# module_connector.net
KiCad netlist of a schematic drawn in EAGLE
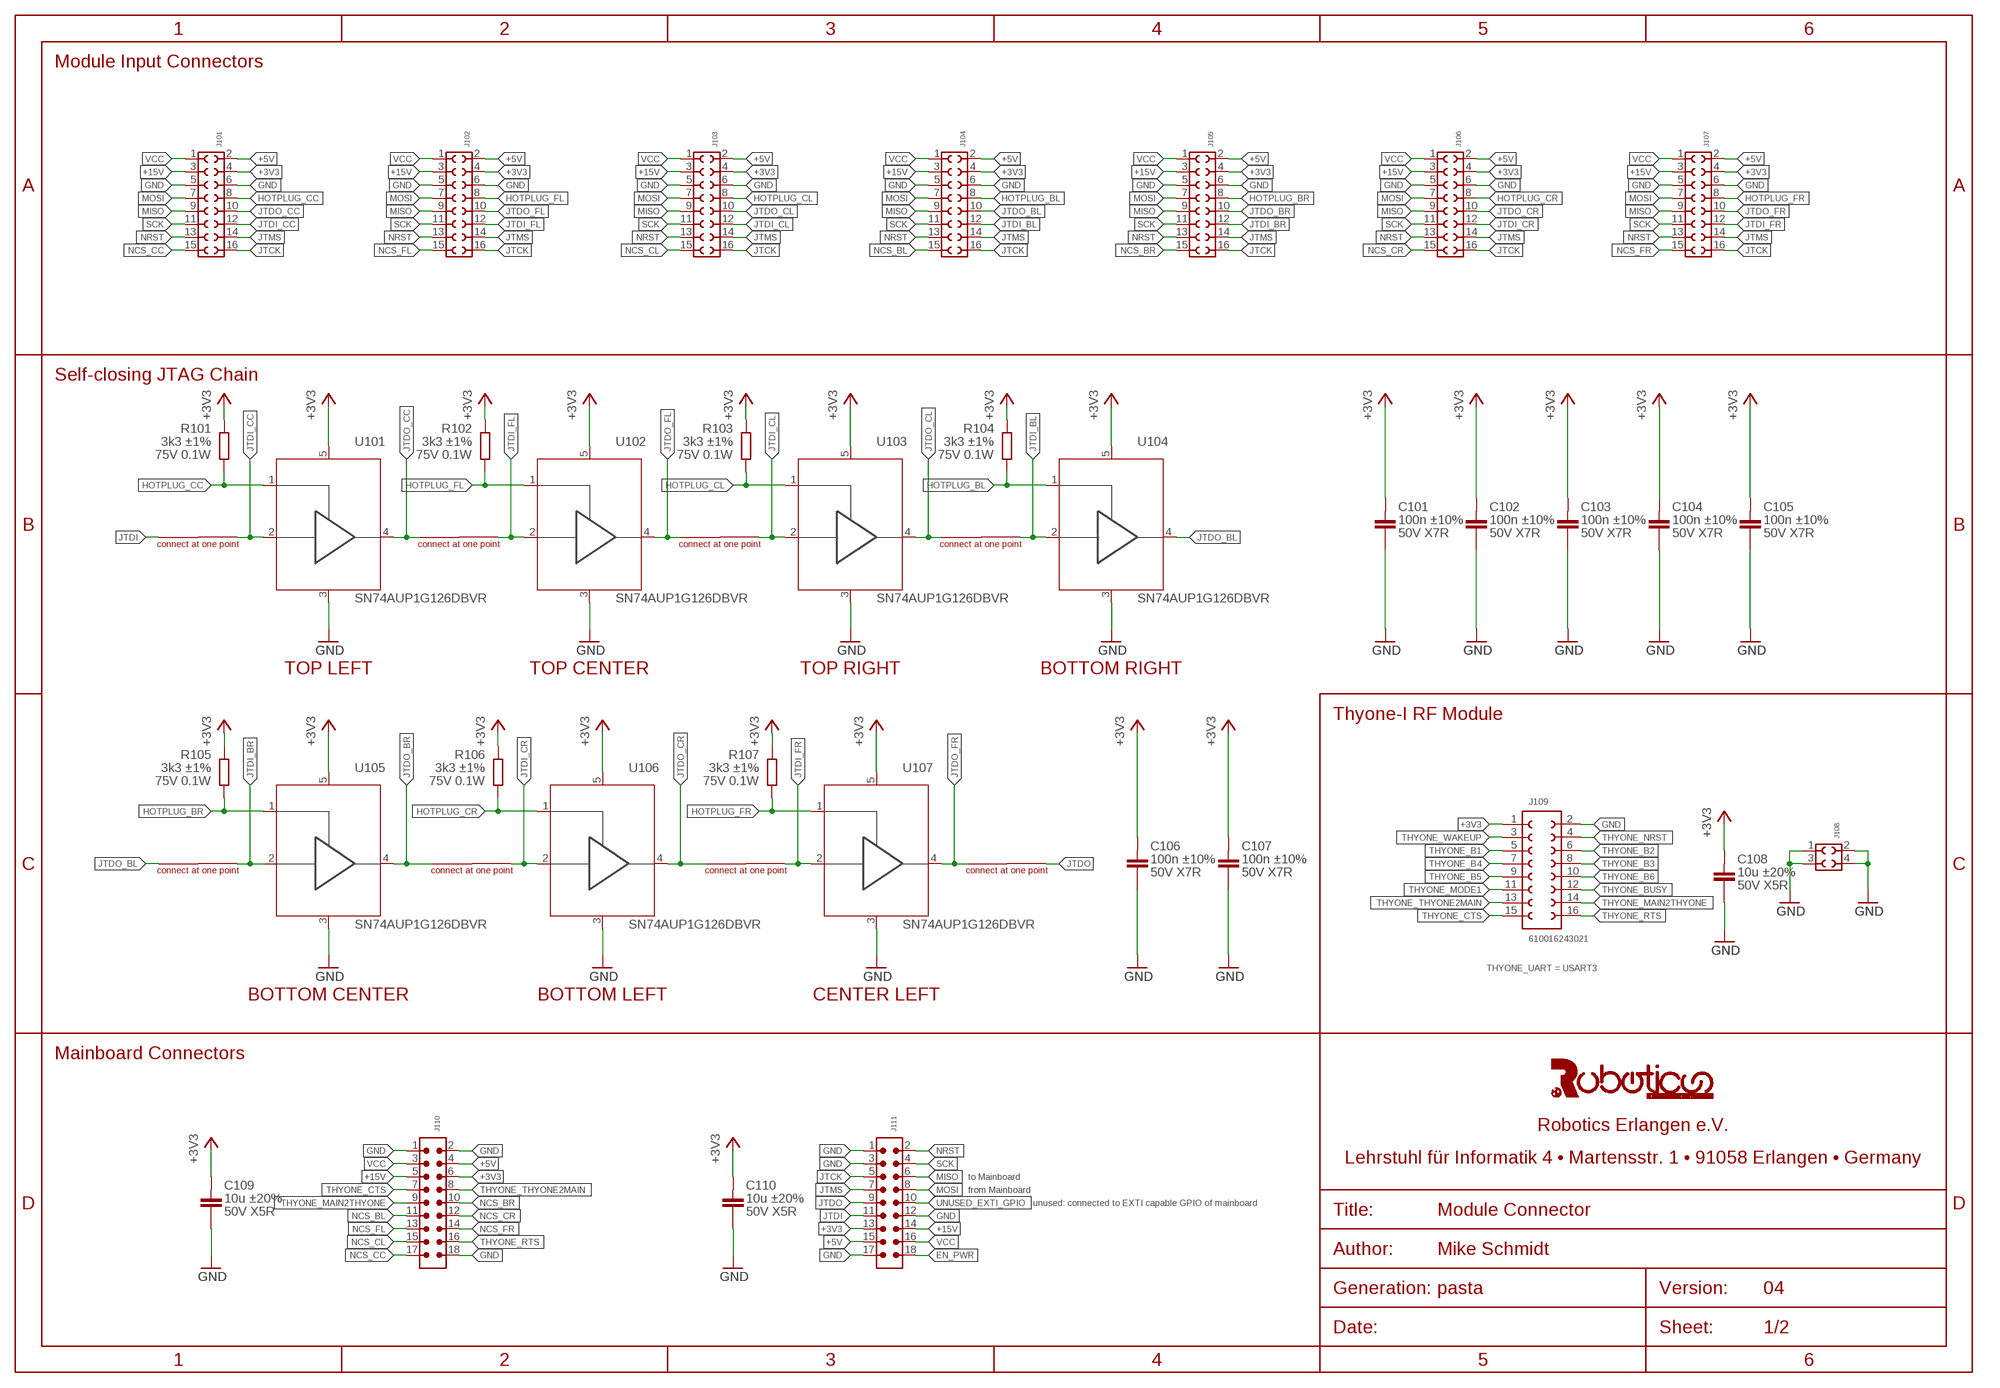
[diagram p0: schematic, sheet 1]
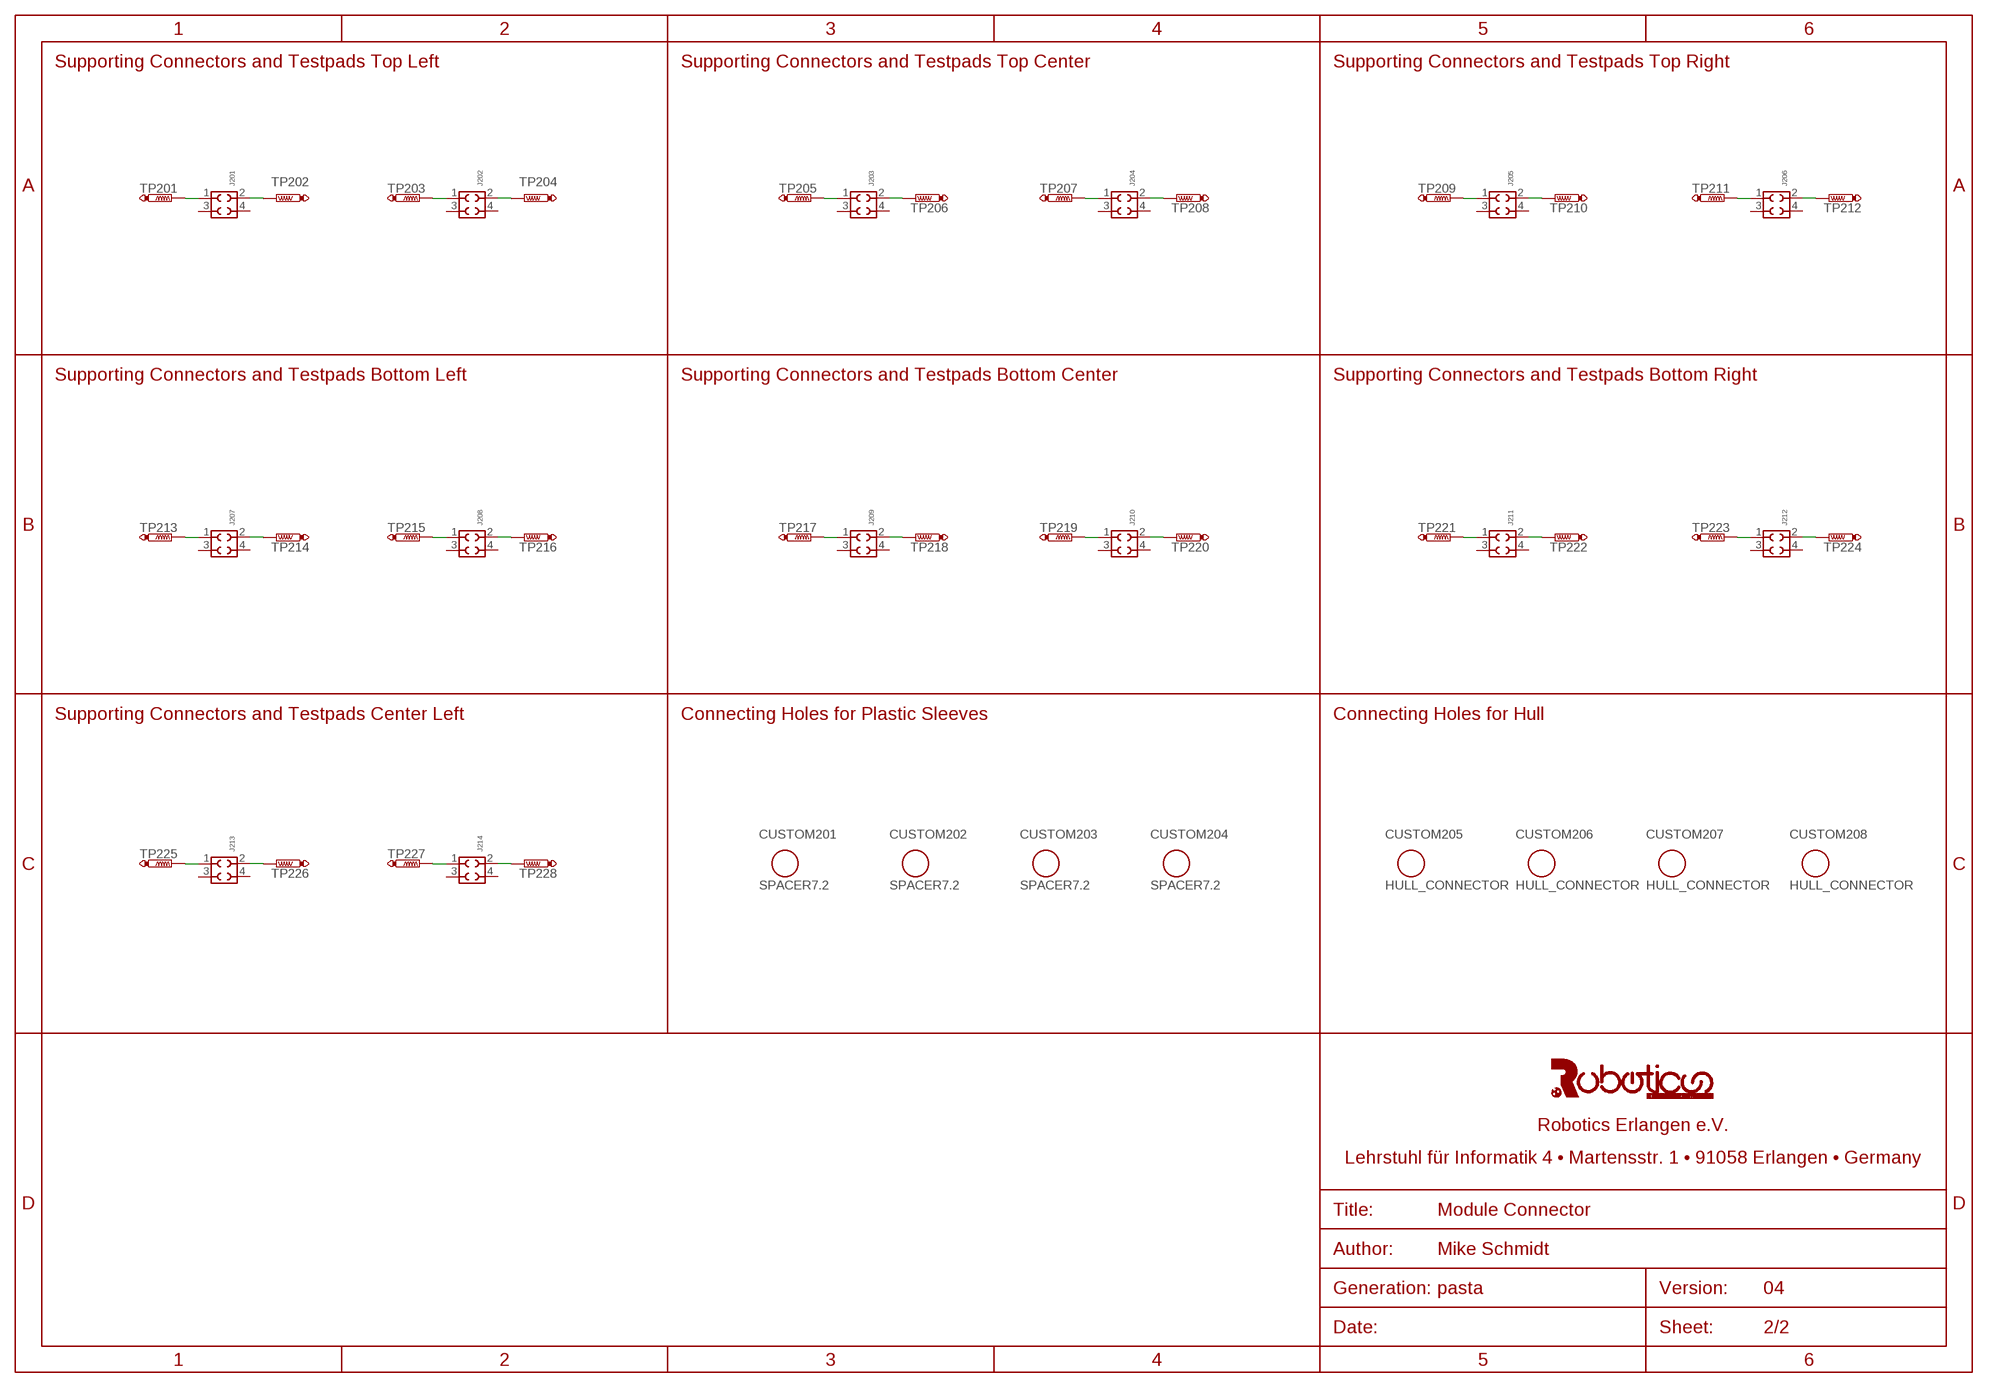
[diagram p1: schematic, sheet 2]

(export (version "E")
  (design (tool "Eeschema 10.0.6"))
  (components
    (comp (ref "C101")
      (value "100n ±10% 50V X7R")
      (footprint "eagle-import:C0603")
      (fields
        (field (name "LINE1") "100n ±10%")
        (field (name "LINE2") "50V X7R")
        (field (name "MF") "Würth Elektronik")
        (field (name "MPN") "885012206095")
        (field (name "TOLERANCE") "±10%")
      )
      (libsource (lib "eagle-import") (part "C(?)0603100NF,50V,"))
    )
    (comp (ref "C102")
      (value "100n ±10% 50V X7R")
      (footprint "eagle-import:C0603")
      (fields
        (field (name "LINE1") "100n ±10%")
        (field (name "LINE2") "50V X7R")
        (field (name "MF") "Würth Elektronik")
        (field (name "MPN") "885012206095")
        (field (name "TOLERANCE") "±10%")
      )
      (libsource (lib "eagle-import") (part "C(?)0603100NF,50V,"))
    )
    (comp (ref "C103")
      (value "100n ±10% 50V X7R")
      (footprint "eagle-import:C0603")
      (fields
        (field (name "LINE1") "100n ±10%")
        (field (name "LINE2") "50V X7R")
        (field (name "MF") "Würth Elektronik")
        (field (name "MPN") "885012206095")
        (field (name "TOLERANCE") "±10%")
      )
      (libsource (lib "eagle-import") (part "C(?)0603100NF,50V,"))
    )
    (comp (ref "C104")
      (value "100n ±10% 50V X7R")
      (footprint "eagle-import:C0603")
      (fields
        (field (name "LINE1") "100n ±10%")
        (field (name "LINE2") "50V X7R")
        (field (name "MF") "Würth Elektronik")
        (field (name "MPN") "885012206095")
        (field (name "TOLERANCE") "±10%")
      )
      (libsource (lib "eagle-import") (part "C(?)0603100NF,50V,"))
    )
    (comp (ref "C105")
      (value "100n ±10% 50V X7R")
      (footprint "eagle-import:C0603")
      (fields
        (field (name "LINE1") "100n ±10%")
        (field (name "LINE2") "50V X7R")
        (field (name "MF") "Würth Elektronik")
        (field (name "MPN") "885012206095")
        (field (name "TOLERANCE") "±10%")
      )
      (libsource (lib "eagle-import") (part "C(?)0603100NF,50V,"))
    )
    (comp (ref "C106")
      (value "100n ±10% 50V X7R")
      (footprint "eagle-import:C0603")
      (fields
        (field (name "LINE1") "100n ±10%")
        (field (name "LINE2") "50V X7R")
        (field (name "MF") "Würth Elektronik")
        (field (name "MPN") "885012206095")
        (field (name "TOLERANCE") "±10%")
      )
      (libsource (lib "eagle-import") (part "C(?)0603100NF,50V,"))
    )
    (comp (ref "C107")
      (value "100n ±10% 50V X7R")
      (footprint "eagle-import:C0603")
      (fields
        (field (name "LINE1") "100n ±10%")
        (field (name "LINE2") "50V X7R")
        (field (name "MF") "Würth Elektronik")
        (field (name "MPN") "885012206095")
        (field (name "TOLERANCE") "±10%")
      )
      (libsource (lib "eagle-import") (part "C(?)0603100NF,50V,"))
    )
    (comp (ref "C108")
      (value "10u ±20% 50V X5R")
      (footprint "eagle-import:C1206")
      (fields
        (field (name "LINE1") "10u ±20%")
        (field (name "LINE2") "50V X5R")
        (field (name "MF") "Samsung")
        (field (name "MPN") "CL31A106MBHNNNE")
        (field (name "TOLERANCE") "±20%")
      )
      (libsource (lib "eagle-import") (part "C(?)120610UF,50V,"))
    )
    (comp (ref "C109")
      (value "10u ±20% 50V X5R")
      (footprint "eagle-import:C1206")
      (fields
        (field (name "LINE1") "10u ±20%")
        (field (name "LINE2") "50V X5R")
        (field (name "MF") "Samsung")
        (field (name "MPN") "CL31A106MBHNNNE")
        (field (name "TOLERANCE") "±20%")
      )
      (libsource (lib "eagle-import") (part "C(?)120610UF,50V,"))
    )
    (comp (ref "C110")
      (value "10u ±20% 50V X5R")
      (footprint "eagle-import:C1206")
      (fields
        (field (name "LINE1") "10u ±20%")
        (field (name "LINE2") "50V X5R")
        (field (name "MF") "Samsung")
        (field (name "MPN") "CL31A106MBHNNNE")
        (field (name "TOLERANCE") "±20%")
      )
      (libsource (lib "eagle-import") (part "C(?)120610UF,50V,"))
    )
    (comp (ref "J101")
      (value "6100XX243021_610016243021")
      (footprint "eagle-import:610016243021")
      (fields (field (name "MF") "Würth Elektronik") (field (name "MPN") "610016243021"))
      (libsource (lib "eagle-import") (part "6100XX243021_610016243021"))
    )
    (comp (ref "J102")
      (value "6100XX243021_610016243021")
      (footprint "eagle-import:610016243021")
      (fields (field (name "MF") "Würth Elektronik") (field (name "MPN") "610016243021"))
      (libsource (lib "eagle-import") (part "6100XX243021_610016243021"))
    )
    (comp (ref "J103")
      (value "6100XX243021_610016243021")
      (footprint "eagle-import:610016243021")
      (fields (field (name "MF") "Würth Elektronik") (field (name "MPN") "610016243021"))
      (libsource (lib "eagle-import") (part "6100XX243021_610016243021"))
    )
    (comp (ref "J104")
      (value "6100XX243021_610016243021")
      (footprint "eagle-import:610016243021")
      (fields (field (name "MF") "Würth Elektronik") (field (name "MPN") "610016243021"))
      (libsource (lib "eagle-import") (part "6100XX243021_610016243021"))
    )
    (comp (ref "J105")
      (value "6100XX243021_610016243021")
      (footprint "eagle-import:610016243021")
      (fields (field (name "MF") "Würth Elektronik") (field (name "MPN") "610016243021"))
      (libsource (lib "eagle-import") (part "6100XX243021_610016243021"))
    )
    (comp (ref "J106")
      (value "6100XX243021_610016243021")
      (footprint "eagle-import:610016243021")
      (fields (field (name "MF") "Würth Elektronik") (field (name "MPN") "610016243021"))
      (libsource (lib "eagle-import") (part "6100XX243021_610016243021"))
    )
    (comp (ref "J107")
      (value "6100XX243021_610016243021")
      (footprint "eagle-import:610016243021")
      (fields (field (name "MF") "Würth Elektronik") (field (name "MPN") "610016243021"))
      (libsource (lib "eagle-import") (part "6100XX243021_610016243021"))
    )
    (comp (ref "J108")
      (value "6100XX243021_610004243021")
      (footprint "eagle-import:610004243021")
      (fields (field (name "MF") "Würth Elektronik") (field (name "MPN") "610004243021"))
      (libsource (lib "eagle-import") (part "6100XX243021_610004243021"))
    )
    (comp (ref "J109")
      (value "610016243021")
      (footprint "eagle-import:610X16243021")
      (fields (field (name "MF") "Würth Elektronik"))
      (libsource (lib "eagle-import") (part "610162430210"))
    )
    (comp (ref "J110")
      (value "6130XX21121_61301821121")
      (footprint "eagle-import:61301821121")
      (fields (field (name "MF") "Würth Elektronik") (field (name "MPN") "61301821121"))
      (libsource (lib "eagle-import") (part "6130XX21121_61301821121"))
    )
    (comp (ref "J111")
      (value "6130XX21121_61301821121")
      (footprint "eagle-import:61301821121")
      (fields (field (name "MF") "Würth Elektronik") (field (name "MPN") "61301821121"))
      (libsource (lib "eagle-import") (part "6130XX21121_61301821121"))
    )
    (comp (ref "R101")
      (value "3k3 ±1% 75V 0.1W")
      (footprint "eagle-import:R0603")
      (fields
        (field (name "LINE1") "3k3 ±1%")
        (field (name "LINE2") "75V 0.1W")
        (field (name "MF") "YAGEO")
        (field (name "MPN") "RC0603FR-073K3L")
        (field (name "POWER") "0.1W")
      )
      (libsource (lib "eagle-import") (part "R(?)06033.3K,75V,0.1W,"))
    )
    (comp (ref "R102")
      (value "3k3 ±1% 75V 0.1W")
      (footprint "eagle-import:R0603")
      (fields
        (field (name "LINE1") "3k3 ±1%")
        (field (name "LINE2") "75V 0.1W")
        (field (name "MF") "YAGEO")
        (field (name "MPN") "RC0603FR-073K3L")
        (field (name "POWER") "0.1W")
      )
      (libsource (lib "eagle-import") (part "R(?)06033.3K,75V,0.1W,"))
    )
    (comp (ref "R103")
      (value "3k3 ±1% 75V 0.1W")
      (footprint "eagle-import:R0603")
      (fields
        (field (name "LINE1") "3k3 ±1%")
        (field (name "LINE2") "75V 0.1W")
        (field (name "MF") "YAGEO")
        (field (name "MPN") "RC0603FR-073K3L")
        (field (name "POWER") "0.1W")
      )
      (libsource (lib "eagle-import") (part "R(?)06033.3K,75V,0.1W,"))
    )
    (comp (ref "R104")
      (value "3k3 ±1% 75V 0.1W")
      (footprint "eagle-import:R0603")
      (fields
        (field (name "LINE1") "3k3 ±1%")
        (field (name "LINE2") "75V 0.1W")
        (field (name "MF") "YAGEO")
        (field (name "MPN") "RC0603FR-073K3L")
        (field (name "POWER") "0.1W")
      )
      (libsource (lib "eagle-import") (part "R(?)06033.3K,75V,0.1W,"))
    )
    (comp (ref "R105")
      (value "3k3 ±1% 75V 0.1W")
      (footprint "eagle-import:R0603")
      (fields
        (field (name "LINE1") "3k3 ±1%")
        (field (name "LINE2") "75V 0.1W")
        (field (name "MF") "YAGEO")
        (field (name "MPN") "RC0603FR-073K3L")
        (field (name "POWER") "0.1W")
      )
      (libsource (lib "eagle-import") (part "R(?)06033.3K,75V,0.1W,"))
    )
    (comp (ref "R106")
      (value "3k3 ±1% 75V 0.1W")
      (footprint "eagle-import:R0603")
      (fields
        (field (name "LINE1") "3k3 ±1%")
        (field (name "LINE2") "75V 0.1W")
        (field (name "MF") "YAGEO")
        (field (name "MPN") "RC0603FR-073K3L")
        (field (name "POWER") "0.1W")
      )
      (libsource (lib "eagle-import") (part "R(?)06033.3K,75V,0.1W,"))
    )
    (comp (ref "R107")
      (value "3k3 ±1% 75V 0.1W")
      (footprint "eagle-import:R0603")
      (fields
        (field (name "LINE1") "3k3 ±1%")
        (field (name "LINE2") "75V 0.1W")
        (field (name "MF") "YAGEO")
        (field (name "MPN") "RC0603FR-073K3L")
        (field (name "POWER") "0.1W")
      )
      (libsource (lib "eagle-import") (part "R(?)06033.3K,75V,0.1W,"))
    )
    (comp (ref "SHORT101")
      (value "SHORT0.254")
      (footprint "eagle-import:SHORT0.254")
      (libsource (lib "eagle-import") (part "SHORT0.254"))
    )
    (comp (ref "SHORT102")
      (value "SHORT0.254")
      (footprint "eagle-import:SHORT0.254")
      (libsource (lib "eagle-import") (part "SHORT0.254"))
    )
    (comp (ref "SHORT103")
      (value "SHORT0.254")
      (footprint "eagle-import:SHORT0.254")
      (libsource (lib "eagle-import") (part "SHORT0.254"))
    )
    (comp (ref "SHORT104")
      (value "SHORT0.254")
      (footprint "eagle-import:SHORT0.254")
      (libsource (lib "eagle-import") (part "SHORT0.254"))
    )
    (comp (ref "SHORT105")
      (value "SHORT0.254")
      (footprint "eagle-import:SHORT0.254")
      (libsource (lib "eagle-import") (part "SHORT0.254"))
    )
    (comp (ref "SHORT106")
      (value "SHORT0.254")
      (footprint "eagle-import:SHORT0.254")
      (libsource (lib "eagle-import") (part "SHORT0.254"))
    )
    (comp (ref "SHORT107")
      (value "SHORT0.254")
      (footprint "eagle-import:SHORT0.254")
      (libsource (lib "eagle-import") (part "SHORT0.254"))
    )
    (comp (ref "SHORT108")
      (value "SHORT0.254")
      (footprint "eagle-import:SHORT0.254")
      (libsource (lib "eagle-import") (part "SHORT0.254"))
    )
    (comp (ref "U101")
      (value "SN74AUP1G126DBVR")
      (footprint "eagle-import:SOT23-5")
      (fields (field (name "MF") "Texas Instruments"))
      (libsource (lib "eagle-import") (part "SN74AUP1G126DBVR"))
    )
    (comp (ref "U102")
      (value "SN74AUP1G126DBVR")
      (footprint "eagle-import:SOT23-5")
      (fields (field (name "MF") "Texas Instruments"))
      (libsource (lib "eagle-import") (part "SN74AUP1G126DBVR"))
    )
    (comp (ref "U103")
      (value "SN74AUP1G126DBVR")
      (footprint "eagle-import:SOT23-5")
      (fields (field (name "MF") "Texas Instruments"))
      (libsource (lib "eagle-import") (part "SN74AUP1G126DBVR"))
    )
    (comp (ref "U104")
      (value "SN74AUP1G126DBVR")
      (footprint "eagle-import:SOT23-5")
      (fields (field (name "MF") "Texas Instruments"))
      (libsource (lib "eagle-import") (part "SN74AUP1G126DBVR"))
    )
    (comp (ref "U105")
      (value "SN74AUP1G126DBVR")
      (footprint "eagle-import:SOT23-5")
      (fields (field (name "MF") "Texas Instruments"))
      (libsource (lib "eagle-import") (part "SN74AUP1G126DBVR"))
    )
    (comp (ref "U106")
      (value "SN74AUP1G126DBVR")
      (footprint "eagle-import:SOT23-5")
      (fields (field (name "MF") "Texas Instruments"))
      (libsource (lib "eagle-import") (part "SN74AUP1G126DBVR"))
    )
    (comp (ref "U107")
      (value "SN74AUP1G126DBVR")
      (footprint "eagle-import:SOT23-5")
      (fields (field (name "MF") "Texas Instruments"))
      (libsource (lib "eagle-import") (part "SN74AUP1G126DBVR"))
    )
    (comp (ref "CUSTOM201")
      (value "SPACER7.2")
      (footprint "eagle-import:PLASTIC_SPACER")
      (libsource (lib "eagle-import") (part "SPACER7.2"))
    )
    (comp (ref "CUSTOM202")
      (value "SPACER7.2")
      (footprint "eagle-import:PLASTIC_SPACER")
      (libsource (lib "eagle-import") (part "SPACER7.2"))
    )
    (comp (ref "CUSTOM203")
      (value "SPACER7.2")
      (footprint "eagle-import:PLASTIC_SPACER")
      (libsource (lib "eagle-import") (part "SPACER7.2"))
    )
    (comp (ref "CUSTOM204")
      (value "SPACER7.2")
      (footprint "eagle-import:PLASTIC_SPACER")
      (libsource (lib "eagle-import") (part "SPACER7.2"))
    )
    (comp (ref "CUSTOM205")
      (value "HULL_CONNECTOR")
      (footprint "eagle-import:HULL_CONNECTOR")
      (libsource (lib "eagle-import") (part "HULL_CONNECTOR"))
    )
    (comp (ref "CUSTOM206")
      (value "HULL_CONNECTOR")
      (footprint "eagle-import:HULL_CONNECTOR")
      (libsource (lib "eagle-import") (part "HULL_CONNECTOR"))
    )
    (comp (ref "CUSTOM207")
      (value "HULL_CONNECTOR")
      (footprint "eagle-import:HULL_CONNECTOR")
      (libsource (lib "eagle-import") (part "HULL_CONNECTOR"))
    )
    (comp (ref "CUSTOM208")
      (value "HULL_CONNECTOR")
      (footprint "eagle-import:HULL_CONNECTOR")
      (libsource (lib "eagle-import") (part "HULL_CONNECTOR"))
    )
    (comp (ref "J201")
      (value "6100XX243021_610004243021")
      (footprint "eagle-import:610004243021")
      (fields (field (name "MF") "Würth Elektronik") (field (name "MPN") "610004243021"))
      (libsource (lib "eagle-import") (part "6100XX243021_610004243021"))
    )
    (comp (ref "J202")
      (value "6100XX243021_610004243021")
      (footprint "eagle-import:610004243021")
      (fields (field (name "MF") "Würth Elektronik") (field (name "MPN") "610004243021"))
      (libsource (lib "eagle-import") (part "6100XX243021_610004243021"))
    )
    (comp (ref "J203")
      (value "6100XX243021_610004243021")
      (footprint "eagle-import:610004243021")
      (fields (field (name "MF") "Würth Elektronik") (field (name "MPN") "610004243021"))
      (libsource (lib "eagle-import") (part "6100XX243021_610004243021"))
    )
    (comp (ref "J204")
      (value "6100XX243021_610004243021")
      (footprint "eagle-import:610004243021")
      (fields (field (name "MF") "Würth Elektronik") (field (name "MPN") "610004243021"))
      (libsource (lib "eagle-import") (part "6100XX243021_610004243021"))
    )
    (comp (ref "J205")
      (value "6100XX243021_610004243021")
      (footprint "eagle-import:610004243021")
      (fields (field (name "MF") "Würth Elektronik") (field (name "MPN") "610004243021"))
      (libsource (lib "eagle-import") (part "6100XX243021_610004243021"))
    )
    (comp (ref "J206")
      (value "6100XX243021_610004243021")
      (footprint "eagle-import:610004243021")
      (fields (field (name "MF") "Würth Elektronik") (field (name "MPN") "610004243021"))
      (libsource (lib "eagle-import") (part "6100XX243021_610004243021"))
    )
    (comp (ref "J207")
      (value "6100XX243021_610004243021")
      (footprint "eagle-import:610004243021")
      (fields (field (name "MF") "Würth Elektronik") (field (name "MPN") "610004243021"))
      (libsource (lib "eagle-import") (part "6100XX243021_610004243021"))
    )
    (comp (ref "J208")
      (value "6100XX243021_610004243021")
      (footprint "eagle-import:610004243021")
      (fields (field (name "MF") "Würth Elektronik") (field (name "MPN") "610004243021"))
      (libsource (lib "eagle-import") (part "6100XX243021_610004243021"))
    )
    (comp (ref "J209")
      (value "6100XX243021_610004243021")
      (footprint "eagle-import:610004243021")
      (fields (field (name "MF") "Würth Elektronik") (field (name "MPN") "610004243021"))
      (libsource (lib "eagle-import") (part "6100XX243021_610004243021"))
    )
    (comp (ref "J210")
      (value "6100XX243021_610004243021")
      (footprint "eagle-import:610004243021")
      (fields (field (name "MF") "Würth Elektronik") (field (name "MPN") "610004243021"))
      (libsource (lib "eagle-import") (part "6100XX243021_610004243021"))
    )
    (comp (ref "J211")
      (value "6100XX243021_610004243021")
      (footprint "eagle-import:610004243021")
      (fields (field (name "MF") "Würth Elektronik") (field (name "MPN") "610004243021"))
      (libsource (lib "eagle-import") (part "6100XX243021_610004243021"))
    )
    (comp (ref "J212")
      (value "6100XX243021_610004243021")
      (footprint "eagle-import:610004243021")
      (fields (field (name "MF") "Würth Elektronik") (field (name "MPN") "610004243021"))
      (libsource (lib "eagle-import") (part "6100XX243021_610004243021"))
    )
    (comp (ref "J213")
      (value "6100XX243021_610004243021")
      (footprint "eagle-import:610004243021")
      (fields (field (name "MF") "Würth Elektronik") (field (name "MPN") "610004243021"))
      (libsource (lib "eagle-import") (part "6100XX243021_610004243021"))
    )
    (comp (ref "J214")
      (value "6100XX243021_610004243021")
      (footprint "eagle-import:610004243021")
      (fields (field (name "MF") "Würth Elektronik") (field (name "MPN") "610004243021"))
      (libsource (lib "eagle-import") (part "6100XX243021_610004243021"))
    )
    (comp (ref "TP201")
      (value "TESTPAD")
      (footprint "eagle-import:TESTPAD")
      (libsource (lib "eagle-import") (part "TESTPAD"))
    )
    (comp (ref "TP202")
      (value "TESTPAD")
      (footprint "eagle-import:TESTPAD")
      (libsource (lib "eagle-import") (part "TESTPAD"))
    )
    (comp (ref "TP203")
      (value "TESTPAD")
      (footprint "eagle-import:TESTPAD")
      (libsource (lib "eagle-import") (part "TESTPAD"))
    )
    (comp (ref "TP204")
      (value "TESTPAD")
      (footprint "eagle-import:TESTPAD")
      (libsource (lib "eagle-import") (part "TESTPAD"))
    )
    (comp (ref "TP205")
      (value "TESTPAD")
      (footprint "eagle-import:TESTPAD")
      (libsource (lib "eagle-import") (part "TESTPAD"))
    )
    (comp (ref "TP206")
      (value "TESTPAD")
      (footprint "eagle-import:TESTPAD")
      (libsource (lib "eagle-import") (part "TESTPAD"))
    )
    (comp (ref "TP207")
      (value "TESTPAD")
      (footprint "eagle-import:TESTPAD")
      (libsource (lib "eagle-import") (part "TESTPAD"))
    )
    (comp (ref "TP208")
      (value "TESTPAD")
      (footprint "eagle-import:TESTPAD")
      (libsource (lib "eagle-import") (part "TESTPAD"))
    )
    (comp (ref "TP209")
      (value "TESTPAD")
      (footprint "eagle-import:TESTPAD")
      (libsource (lib "eagle-import") (part "TESTPAD"))
    )
    (comp (ref "TP210")
      (value "TESTPAD")
      (footprint "eagle-import:TESTPAD")
      (libsource (lib "eagle-import") (part "TESTPAD"))
    )
    (comp (ref "TP211")
      (value "TESTPAD")
      (footprint "eagle-import:TESTPAD")
      (libsource (lib "eagle-import") (part "TESTPAD"))
    )
    (comp (ref "TP212")
      (value "TESTPAD")
      (footprint "eagle-import:TESTPAD")
      (libsource (lib "eagle-import") (part "TESTPAD"))
    )
    (comp (ref "TP213")
      (value "TESTPAD")
      (footprint "eagle-import:TESTPAD")
      (libsource (lib "eagle-import") (part "TESTPAD"))
    )
    (comp (ref "TP214")
      (value "TESTPAD")
      (footprint "eagle-import:TESTPAD")
      (libsource (lib "eagle-import") (part "TESTPAD"))
    )
    (comp (ref "TP215")
      (value "TESTPAD")
      (footprint "eagle-import:TESTPAD")
      (libsource (lib "eagle-import") (part "TESTPAD"))
    )
    (comp (ref "TP216")
      (value "TESTPAD")
      (footprint "eagle-import:TESTPAD")
      (libsource (lib "eagle-import") (part "TESTPAD"))
    )
    (comp (ref "TP217")
      (value "TESTPAD")
      (footprint "eagle-import:TESTPAD")
      (libsource (lib "eagle-import") (part "TESTPAD"))
    )
    (comp (ref "TP218")
      (value "TESTPAD")
      (footprint "eagle-import:TESTPAD")
      (libsource (lib "eagle-import") (part "TESTPAD"))
    )
    (comp (ref "TP219")
      (value "TESTPAD")
      (footprint "eagle-import:TESTPAD")
      (libsource (lib "eagle-import") (part "TESTPAD"))
    )
    (comp (ref "TP220")
      (value "TESTPAD")
      (footprint "eagle-import:TESTPAD")
      (libsource (lib "eagle-import") (part "TESTPAD"))
    )
    (comp (ref "TP221")
      (value "TESTPAD")
      (footprint "eagle-import:TESTPAD")
      (libsource (lib "eagle-import") (part "TESTPAD"))
    )
    (comp (ref "TP222")
      (value "TESTPAD")
      (footprint "eagle-import:TESTPAD")
      (libsource (lib "eagle-import") (part "TESTPAD"))
    )
    (comp (ref "TP223")
      (value "TESTPAD")
      (footprint "eagle-import:TESTPAD")
      (libsource (lib "eagle-import") (part "TESTPAD"))
    )
    (comp (ref "TP224")
      (value "TESTPAD")
      (footprint "eagle-import:TESTPAD")
      (libsource (lib "eagle-import") (part "TESTPAD"))
    )
    (comp (ref "TP225")
      (value "TESTPAD")
      (footprint "eagle-import:TESTPAD")
      (libsource (lib "eagle-import") (part "TESTPAD"))
    )
    (comp (ref "TP226")
      (value "TESTPAD")
      (footprint "eagle-import:TESTPAD")
      (libsource (lib "eagle-import") (part "TESTPAD"))
    )
    (comp (ref "TP227")
      (value "TESTPAD")
      (footprint "eagle-import:TESTPAD")
      (libsource (lib "eagle-import") (part "TESTPAD"))
    )
    (comp (ref "TP228")
      (value "TESTPAD")
      (footprint "eagle-import:TESTPAD")
      (libsource (lib "eagle-import") (part "TESTPAD"))
    )
  )
  (nets
    (net (code "1") (name "+3V3") (class "Default")
      (node (ref "C101") (pin "1") (pinfunction "1_1") (pintype "passive"))
      (node (ref "C102") (pin "1") (pinfunction "1_1") (pintype "passive"))
      (node (ref "C103") (pin "1") (pinfunction "1_1") (pintype "passive"))
      (node (ref "C104") (pin "1") (pinfunction "1_1") (pintype "passive"))
      (node (ref "C105") (pin "1") (pinfunction "1_1") (pintype "passive"))
      (node (ref "C106") (pin "1") (pinfunction "1_1") (pintype "passive"))
      (node (ref "C107") (pin "1") (pinfunction "1_1") (pintype "passive"))
      (node (ref "C108") (pin "1") (pinfunction "1_1") (pintype "passive"))
      (node (ref "C109") (pin "1") (pinfunction "1_1") (pintype "passive"))
      (node (ref "C110") (pin "1") (pinfunction "1_1") (pintype "passive"))
      (node (ref "J101") (pin "4") (pinfunction "4_4") (pintype "passive"))
      (node (ref "J102") (pin "4") (pinfunction "4_4") (pintype "passive"))
      (node (ref "J103") (pin "4") (pinfunction "4_4") (pintype "passive"))
      (node (ref "J104") (pin "4") (pinfunction "4_4") (pintype "passive"))
      (node (ref "J105") (pin "4") (pinfunction "4_4") (pintype "passive"))
      (node (ref "J106") (pin "4") (pinfunction "4_4") (pintype "passive"))
      (node (ref "J107") (pin "4") (pinfunction "4_4") (pintype "passive"))
      (node (ref "J109") (pin "1") (pinfunction "1_1") (pintype "passive"))
      (node (ref "J110") (pin "6") (pinfunction "6_6") (pintype "passive"))
      (node (ref "J111") (pin "13") (pinfunction "13_13") (pintype "passive"))
      (node (ref "R101") (pin "2") (pinfunction "2_2") (pintype "passive"))
      (node (ref "R102") (pin "2") (pinfunction "2_2") (pintype "passive"))
      (node (ref "R103") (pin "2") (pinfunction "2_2") (pintype "passive"))
      (node (ref "R104") (pin "2") (pinfunction "2_2") (pintype "passive"))
      (node (ref "R105") (pin "2") (pinfunction "2_2") (pintype "passive"))
      (node (ref "R106") (pin "2") (pinfunction "2_2") (pintype "passive"))
      (node (ref "R107") (pin "2") (pinfunction "2_2") (pintype "passive"))
      (node (ref "U101") (pin "5") (pinfunction "VCC_5") (pintype "power_in"))
      (node (ref "U102") (pin "5") (pinfunction "VCC_5") (pintype "power_in"))
      (node (ref "U103") (pin "5") (pinfunction "VCC_5") (pintype "power_in"))
      (node (ref "U104") (pin "5") (pinfunction "VCC_5") (pintype "power_in"))
      (node (ref "U105") (pin "5") (pinfunction "VCC_5") (pintype "power_in"))
      (node (ref "U106") (pin "5") (pinfunction "VCC_5") (pintype "power_in"))
      (node (ref "U107") (pin "5") (pinfunction "VCC_5") (pintype "power_in"))
    )
    (net (code "2") (name "+5V") (class "Default")
      (node (ref "J101") (pin "2") (pinfunction "2_2") (pintype "passive"))
      (node (ref "J102") (pin "2") (pinfunction "2_2") (pintype "passive"))
      (node (ref "J103") (pin "2") (pinfunction "2_2") (pintype "passive"))
      (node (ref "J104") (pin "2") (pinfunction "2_2") (pintype "passive"))
      (node (ref "J105") (pin "2") (pinfunction "2_2") (pintype "passive"))
      (node (ref "J106") (pin "2") (pinfunction "2_2") (pintype "passive"))
      (node (ref "J107") (pin "2") (pinfunction "2_2") (pintype "passive"))
      (node (ref "J110") (pin "4") (pinfunction "4_4") (pintype "passive"))
      (node (ref "J111") (pin "15") (pinfunction "15_15") (pintype "passive"))
    )
    (net (code "3") (name "+15V") (class "Default")
      (node (ref "J101") (pin "3") (pinfunction "3_3") (pintype "passive"))
      (node (ref "J102") (pin "3") (pinfunction "3_3") (pintype "passive"))
      (node (ref "J103") (pin "3") (pinfunction "3_3") (pintype "passive"))
      (node (ref "J104") (pin "3") (pinfunction "3_3") (pintype "passive"))
      (node (ref "J105") (pin "3") (pinfunction "3_3") (pintype "passive"))
      (node (ref "J106") (pin "3") (pinfunction "3_3") (pintype "passive"))
      (node (ref "J107") (pin "3") (pinfunction "3_3") (pintype "passive"))
      (node (ref "J110") (pin "5") (pinfunction "5_5") (pintype "passive"))
      (node (ref "J111") (pin "14") (pinfunction "14_14") (pintype "passive"))
    )
    (net (code "4") (name "EN_PWR") (class "Default")
      (node (ref "J111") (pin "18") (pinfunction "18_18") (pintype "passive"))
    )
    (net (code "5") (name "GND") (class "Default")
      (node (ref "C101") (pin "2") (pinfunction "2_2") (pintype "passive"))
      (node (ref "C102") (pin "2") (pinfunction "2_2") (pintype "passive"))
      (node (ref "C103") (pin "2") (pinfunction "2_2") (pintype "passive"))
      (node (ref "C104") (pin "2") (pinfunction "2_2") (pintype "passive"))
      (node (ref "C105") (pin "2") (pinfunction "2_2") (pintype "passive"))
      (node (ref "C106") (pin "2") (pinfunction "2_2") (pintype "passive"))
      (node (ref "C107") (pin "2") (pinfunction "2_2") (pintype "passive"))
      (node (ref "C108") (pin "2") (pinfunction "2_2") (pintype "passive"))
      (node (ref "C109") (pin "2") (pinfunction "2_2") (pintype "passive"))
      (node (ref "C110") (pin "2") (pinfunction "2_2") (pintype "passive"))
      (node (ref "J101") (pin "5") (pinfunction "5_5") (pintype "passive"))
      (node (ref "J101") (pin "6") (pinfunction "6_6") (pintype "passive"))
      (node (ref "J102") (pin "5") (pinfunction "5_5") (pintype "passive"))
      (node (ref "J102") (pin "6") (pinfunction "6_6") (pintype "passive"))
      (node (ref "J103") (pin "5") (pinfunction "5_5") (pintype "passive"))
      (node (ref "J103") (pin "6") (pinfunction "6_6") (pintype "passive"))
      (node (ref "J104") (pin "5") (pinfunction "5_5") (pintype "passive"))
      (node (ref "J104") (pin "6") (pinfunction "6_6") (pintype "passive"))
      (node (ref "J105") (pin "5") (pinfunction "5_5") (pintype "passive"))
      (node (ref "J105") (pin "6") (pinfunction "6_6") (pintype "passive"))
      (node (ref "J106") (pin "5") (pinfunction "5_5") (pintype "passive"))
      (node (ref "J106") (pin "6") (pinfunction "6_6") (pintype "passive"))
      (node (ref "J107") (pin "5") (pinfunction "5_5") (pintype "passive"))
      (node (ref "J107") (pin "6") (pinfunction "6_6") (pintype "passive"))
      (node (ref "J108") (pin "1") (pinfunction "1_1") (pintype "passive"))
      (node (ref "J108") (pin "2") (pinfunction "2_2") (pintype "passive"))
      (node (ref "J108") (pin "3") (pinfunction "3_3") (pintype "passive"))
      (node (ref "J108") (pin "4") (pinfunction "4_4") (pintype "passive"))
      (node (ref "J109") (pin "2") (pinfunction "16_2") (pintype "passive"))
      (node (ref "J110") (pin "1") (pinfunction "1_1") (pintype "passive"))
      (node (ref "J110") (pin "18") (pinfunction "18_18") (pintype "passive"))
      (node (ref "J110") (pin "2") (pinfunction "2_2") (pintype "passive"))
      (node (ref "J111") (pin "1") (pinfunction "1_1") (pintype "passive"))
      (node (ref "J111") (pin "12") (pinfunction "12_12") (pintype "passive"))
      (node (ref "J111") (pin "17") (pinfunction "17_17") (pintype "passive"))
      (node (ref "J111") (pin "3") (pinfunction "3_3") (pintype "passive"))
      (node (ref "U101") (pin "3") (pinfunction "GND_3") (pintype "power_in"))
      (node (ref "U102") (pin "3") (pinfunction "GND_3") (pintype "power_in"))
      (node (ref "U103") (pin "3") (pinfunction "GND_3") (pintype "power_in"))
      (node (ref "U104") (pin "3") (pinfunction "GND_3") (pintype "power_in"))
      (node (ref "U105") (pin "3") (pinfunction "GND_3") (pintype "power_in"))
      (node (ref "U106") (pin "3") (pinfunction "GND_3") (pintype "power_in"))
      (node (ref "U107") (pin "3") (pinfunction "GND_3") (pintype "power_in"))
    )
    (net (code "6") (name "HOTPLUG_BL") (class "Default")
      (node (ref "J104") (pin "8") (pinfunction "8_8") (pintype "passive"))
      (node (ref "R104") (pin "1") (pinfunction "1_1") (pintype "passive"))
      (node (ref "U104") (pin "1") (pinfunction "OE_1") (pintype "input"))
    )
    (net (code "7") (name "HOTPLUG_BR") (class "Default")
      (node (ref "J105") (pin "8") (pinfunction "8_8") (pintype "passive"))
      (node (ref "R105") (pin "1") (pinfunction "1_1") (pintype "passive"))
      (node (ref "U105") (pin "1") (pinfunction "OE_1") (pintype "input"))
    )
    (net (code "8") (name "HOTPLUG_CC") (class "Default")
      (node (ref "J101") (pin "8") (pinfunction "8_8") (pintype "passive"))
      (node (ref "R101") (pin "1") (pinfunction "1_1") (pintype "passive"))
      (node (ref "U101") (pin "1") (pinfunction "OE_1") (pintype "input"))
    )
    (net (code "9") (name "HOTPLUG_CL") (class "Default")
      (node (ref "J103") (pin "8") (pinfunction "8_8") (pintype "passive"))
      (node (ref "R103") (pin "1") (pinfunction "1_1") (pintype "passive"))
      (node (ref "U103") (pin "1") (pinfunction "OE_1") (pintype "input"))
    )
    (net (code "10") (name "HOTPLUG_CR") (class "Default")
      (node (ref "J106") (pin "8") (pinfunction "8_8") (pintype "passive"))
      (node (ref "R106") (pin "1") (pinfunction "1_1") (pintype "passive"))
      (node (ref "U106") (pin "1") (pinfunction "OE_1") (pintype "input"))
    )
    (net (code "11") (name "HOTPLUG_FL") (class "Default")
      (node (ref "J102") (pin "8") (pinfunction "8_8") (pintype "passive"))
      (node (ref "R102") (pin "1") (pinfunction "1_1") (pintype "passive"))
      (node (ref "U102") (pin "1") (pinfunction "OE_1") (pintype "input"))
    )
    (net (code "12") (name "HOTPLUG_FR") (class "Default")
      (node (ref "J107") (pin "8") (pinfunction "8_8") (pintype "passive"))
      (node (ref "R107") (pin "1") (pinfunction "1_1") (pintype "passive"))
      (node (ref "U107") (pin "1") (pinfunction "OE_1") (pintype "input"))
    )
    (net (code "13") (name "JTCK") (class "Default")
      (node (ref "J101") (pin "16") (pinfunction "16_16") (pintype "passive"))
      (node (ref "J102") (pin "16") (pinfunction "16_16") (pintype "passive"))
      (node (ref "J103") (pin "16") (pinfunction "16_16") (pintype "passive"))
      (node (ref "J104") (pin "16") (pinfunction "16_16") (pintype "passive"))
      (node (ref "J105") (pin "16") (pinfunction "16_16") (pintype "passive"))
      (node (ref "J106") (pin "16") (pinfunction "16_16") (pintype "passive"))
      (node (ref "J107") (pin "16") (pinfunction "16_16") (pintype "passive"))
      (node (ref "J111") (pin "5") (pinfunction "5_5") (pintype "passive"))
    )
    (net (code "14") (name "JTDI") (class "Default")
      (node (ref "J111") (pin "11") (pinfunction "11_11") (pintype "passive"))
      (node (ref "SHORT101") (pin "P1") (pinfunction "P$1_P1") (pintype "bidirectional"))
    )
    (net (code "15") (name "JTDI_BL") (class "Default")
      (node (ref "J104") (pin "12") (pinfunction "12_12") (pintype "passive"))
      (node (ref "SHORT104") (pin "P2") (pinfunction "P$2_P2") (pintype "bidirectional"))
      (node (ref "U104") (pin "2") (pinfunction "I_2") (pintype "input"))
    )
    (net (code "16") (name "JTDI_BR") (class "Default")
      (node (ref "J105") (pin "12") (pinfunction "12_12") (pintype "passive"))
      (node (ref "SHORT105") (pin "P2") (pinfunction "P$2_P2") (pintype "bidirectional"))
      (node (ref "U105") (pin "2") (pinfunction "I_2") (pintype "input"))
    )
    (net (code "17") (name "JTDI_CC") (class "Default")
      (node (ref "J101") (pin "12") (pinfunction "12_12") (pintype "passive"))
      (node (ref "SHORT101") (pin "P2") (pinfunction "P$2_P2") (pintype "bidirectional"))
      (node (ref "U101") (pin "2") (pinfunction "I_2") (pintype "input"))
    )
    (net (code "18") (name "JTDI_CL") (class "Default")
      (node (ref "J103") (pin "12") (pinfunction "12_12") (pintype "passive"))
      (node (ref "SHORT103") (pin "P2") (pinfunction "P$2_P2") (pintype "bidirectional"))
      (node (ref "U103") (pin "2") (pinfunction "I_2") (pintype "input"))
    )
    (net (code "19") (name "JTDI_CR") (class "Default")
      (node (ref "J106") (pin "12") (pinfunction "12_12") (pintype "passive"))
      (node (ref "SHORT106") (pin "P2") (pinfunction "P$2_P2") (pintype "bidirectional"))
      (node (ref "U106") (pin "2") (pinfunction "I_2") (pintype "input"))
    )
    (net (code "20") (name "JTDI_FL") (class "Default")
      (node (ref "J102") (pin "12") (pinfunction "12_12") (pintype "passive"))
      (node (ref "SHORT102") (pin "P2") (pinfunction "P$2_P2") (pintype "bidirectional"))
      (node (ref "U102") (pin "2") (pinfunction "I_2") (pintype "input"))
    )
    (net (code "21") (name "JTDI_FR") (class "Default")
      (node (ref "J107") (pin "12") (pinfunction "12_12") (pintype "passive"))
      (node (ref "SHORT107") (pin "P2") (pinfunction "P$2_P2") (pintype "bidirectional"))
      (node (ref "U107") (pin "2") (pinfunction "I_2") (pintype "input"))
    )
    (net (code "22") (name "JTDO") (class "Default")
      (node (ref "J111") (pin "9") (pinfunction "9_9") (pintype "passive"))
      (node (ref "SHORT108") (pin "P2") (pinfunction "P$2_P2") (pintype "bidirectional"))
    )
    (net (code "23") (name "JTDO_BL") (class "Default")
      (node (ref "J104") (pin "10") (pinfunction "10_10") (pintype "passive"))
      (node (ref "SHORT105") (pin "P1") (pinfunction "P$1_P1") (pintype "bidirectional"))
      (node (ref "U104") (pin "4") (pinfunction "O_4") (pintype "tri_state"))
    )
    (net (code "24") (name "JTDO_BR") (class "Default")
      (node (ref "J105") (pin "10") (pinfunction "10_10") (pintype "passive"))
      (node (ref "SHORT106") (pin "P1") (pinfunction "P$1_P1") (pintype "bidirectional"))
      (node (ref "U105") (pin "4") (pinfunction "O_4") (pintype "tri_state"))
    )
    (net (code "25") (name "JTDO_CC") (class "Default")
      (node (ref "J101") (pin "10") (pinfunction "10_10") (pintype "passive"))
      (node (ref "SHORT102") (pin "P1") (pinfunction "P$1_P1") (pintype "bidirectional"))
      (node (ref "U101") (pin "4") (pinfunction "O_4") (pintype "tri_state"))
    )
    (net (code "26") (name "JTDO_CL") (class "Default")
      (node (ref "J103") (pin "10") (pinfunction "10_10") (pintype "passive"))
      (node (ref "SHORT104") (pin "P1") (pinfunction "P$1_P1") (pintype "bidirectional"))
      (node (ref "U103") (pin "4") (pinfunction "O_4") (pintype "tri_state"))
    )
    (net (code "27") (name "JTDO_CR") (class "Default")
      (node (ref "J106") (pin "10") (pinfunction "10_10") (pintype "passive"))
      (node (ref "SHORT107") (pin "P1") (pinfunction "P$1_P1") (pintype "bidirectional"))
      (node (ref "U106") (pin "4") (pinfunction "O_4") (pintype "tri_state"))
    )
    (net (code "28") (name "JTDO_FL") (class "Default")
      (node (ref "J102") (pin "10") (pinfunction "10_10") (pintype "passive"))
      (node (ref "SHORT103") (pin "P1") (pinfunction "P$1_P1") (pintype "bidirectional"))
      (node (ref "U102") (pin "4") (pinfunction "O_4") (pintype "tri_state"))
    )
    (net (code "29") (name "JTDO_FR") (class "Default")
      (node (ref "J107") (pin "10") (pinfunction "10_10") (pintype "passive"))
      (node (ref "SHORT108") (pin "P1") (pinfunction "P$1_P1") (pintype "bidirectional"))
      (node (ref "U107") (pin "4") (pinfunction "O_4") (pintype "tri_state"))
    )
    (net (code "30") (name "JTMS") (class "Default")
      (node (ref "J101") (pin "14") (pinfunction "14_14") (pintype "passive"))
      (node (ref "J102") (pin "14") (pinfunction "14_14") (pintype "passive"))
      (node (ref "J103") (pin "14") (pinfunction "14_14") (pintype "passive"))
      (node (ref "J104") (pin "14") (pinfunction "14_14") (pintype "passive"))
      (node (ref "J105") (pin "14") (pinfunction "14_14") (pintype "passive"))
      (node (ref "J106") (pin "14") (pinfunction "14_14") (pintype "passive"))
      (node (ref "J107") (pin "14") (pinfunction "14_14") (pintype "passive"))
      (node (ref "J111") (pin "7") (pinfunction "7_7") (pintype "passive"))
    )
    (net (code "31") (name "MISO") (class "Default")
      (node (ref "J101") (pin "9") (pinfunction "9_9") (pintype "passive"))
      (node (ref "J102") (pin "9") (pinfunction "9_9") (pintype "passive"))
      (node (ref "J103") (pin "9") (pinfunction "9_9") (pintype "passive"))
      (node (ref "J104") (pin "9") (pinfunction "9_9") (pintype "passive"))
      (node (ref "J105") (pin "9") (pinfunction "9_9") (pintype "passive"))
      (node (ref "J106") (pin "9") (pinfunction "9_9") (pintype "passive"))
      (node (ref "J107") (pin "9") (pinfunction "9_9") (pintype "passive"))
      (node (ref "J111") (pin "6") (pinfunction "6_6") (pintype "passive"))
    )
    (net (code "32") (name "MOSI") (class "Default")
      (node (ref "J101") (pin "7") (pinfunction "7_7") (pintype "passive"))
      (node (ref "J102") (pin "7") (pinfunction "7_7") (pintype "passive"))
      (node (ref "J103") (pin "7") (pinfunction "7_7") (pintype "passive"))
      (node (ref "J104") (pin "7") (pinfunction "7_7") (pintype "passive"))
      (node (ref "J105") (pin "7") (pinfunction "7_7") (pintype "passive"))
      (node (ref "J106") (pin "7") (pinfunction "7_7") (pintype "passive"))
      (node (ref "J107") (pin "7") (pinfunction "7_7") (pintype "passive"))
      (node (ref "J111") (pin "8") (pinfunction "8_8") (pintype "passive"))
    )
    (net (code "33") (name "NCS_BL") (class "Default")
      (node (ref "J104") (pin "15") (pinfunction "15_15") (pintype "passive"))
      (node (ref "J110") (pin "11") (pinfunction "11_11") (pintype "passive"))
    )
    (net (code "34") (name "NCS_BR") (class "Default")
      (node (ref "J105") (pin "15") (pinfunction "15_15") (pintype "passive"))
      (node (ref "J110") (pin "10") (pinfunction "10_10") (pintype "passive"))
    )
    (net (code "35") (name "NCS_CC") (class "Default")
      (node (ref "J101") (pin "15") (pinfunction "15_15") (pintype "passive"))
      (node (ref "J110") (pin "17") (pinfunction "17_17") (pintype "passive"))
    )
    (net (code "36") (name "NCS_CL") (class "Default")
      (node (ref "J103") (pin "15") (pinfunction "15_15") (pintype "passive"))
      (node (ref "J110") (pin "15") (pinfunction "15_15") (pintype "passive"))
    )
    (net (code "37") (name "NCS_CR") (class "Default")
      (node (ref "J106") (pin "15") (pinfunction "15_15") (pintype "passive"))
      (node (ref "J110") (pin "12") (pinfunction "12_12") (pintype "passive"))
    )
    (net (code "38") (name "NCS_FL") (class "Default")
      (node (ref "J102") (pin "15") (pinfunction "15_15") (pintype "passive"))
      (node (ref "J110") (pin "13") (pinfunction "13_13") (pintype "passive"))
    )
    (net (code "39") (name "NCS_FR") (class "Default")
      (node (ref "J107") (pin "15") (pinfunction "15_15") (pintype "passive"))
      (node (ref "J110") (pin "14") (pinfunction "14_14") (pintype "passive"))
    )
    (net (code "40") (name "NRST") (class "Default")
      (node (ref "J101") (pin "13") (pinfunction "13_13") (pintype "passive"))
      (node (ref "J102") (pin "13") (pinfunction "13_13") (pintype "passive"))
      (node (ref "J103") (pin "13") (pinfunction "13_13") (pintype "passive"))
      (node (ref "J104") (pin "13") (pinfunction "13_13") (pintype "passive"))
      (node (ref "J105") (pin "13") (pinfunction "13_13") (pintype "passive"))
      (node (ref "J106") (pin "13") (pinfunction "13_13") (pintype "passive"))
      (node (ref "J107") (pin "13") (pinfunction "13_13") (pintype "passive"))
      (node (ref "J111") (pin "2") (pinfunction "2_2") (pintype "passive"))
    )
    (net (code "41") (name "Net-(TP201-TP)") (class "Default")
      (node (ref "J201") (pin "1") (pinfunction "1_1") (pintype "passive"))
      (node (ref "TP201") (pin "P$1") (pinfunction "TP_P$1") (pintype "input"))
    )
    (net (code "42") (name "Net-(TP202-TP)") (class "Default")
      (node (ref "J201") (pin "2") (pinfunction "2_2") (pintype "passive"))
      (node (ref "TP202") (pin "P$1") (pinfunction "TP_P$1") (pintype "input"))
    )
    (net (code "43") (name "Net-(TP203-TP)") (class "Default")
      (node (ref "J202") (pin "1") (pinfunction "1_1") (pintype "passive"))
      (node (ref "TP203") (pin "P$1") (pinfunction "TP_P$1") (pintype "input"))
    )
    (net (code "44") (name "Net-(TP204-TP)") (class "Default")
      (node (ref "J202") (pin "2") (pinfunction "2_2") (pintype "passive"))
      (node (ref "TP204") (pin "P$1") (pinfunction "TP_P$1") (pintype "input"))
    )
    (net (code "45") (name "Net-(TP205-TP)") (class "Default")
      (node (ref "J203") (pin "1") (pinfunction "1_1") (pintype "passive"))
      (node (ref "TP205") (pin "P$1") (pinfunction "TP_P$1") (pintype "input"))
    )
    (net (code "46") (name "Net-(TP206-TP)") (class "Default")
      (node (ref "J203") (pin "2") (pinfunction "2_2") (pintype "passive"))
      (node (ref "TP206") (pin "P$1") (pinfunction "TP_P$1") (pintype "input"))
    )
    (net (code "47") (name "Net-(TP207-TP)") (class "Default")
      (node (ref "J204") (pin "1") (pinfunction "1_1") (pintype "passive"))
      (node (ref "TP207") (pin "P$1") (pinfunction "TP_P$1") (pintype "input"))
    )
    (net (code "48") (name "Net-(TP208-TP)") (class "Default")
      (node (ref "J204") (pin "2") (pinfunction "2_2") (pintype "passive"))
      (node (ref "TP208") (pin "P$1") (pinfunction "TP_P$1") (pintype "input"))
    )
    (net (code "49") (name "Net-(TP209-TP)") (class "Default")
      (node (ref "J205") (pin "1") (pinfunction "1_1") (pintype "passive"))
      (node (ref "TP209") (pin "P$1") (pinfunction "TP_P$1") (pintype "input"))
    )
    (net (code "50") (name "Net-(TP210-TP)") (class "Default")
      (node (ref "J205") (pin "2") (pinfunction "2_2") (pintype "passive"))
      (node (ref "TP210") (pin "P$1") (pinfunction "TP_P$1") (pintype "input"))
    )
    (net (code "51") (name "Net-(TP211-TP)") (class "Default")
      (node (ref "J206") (pin "1") (pinfunction "1_1") (pintype "passive"))
      (node (ref "TP211") (pin "P$1") (pinfunction "TP_P$1") (pintype "input"))
    )
    (net (code "52") (name "Net-(TP212-TP)") (class "Default")
      (node (ref "J206") (pin "2") (pinfunction "2_2") (pintype "passive"))
      (node (ref "TP212") (pin "P$1") (pinfunction "TP_P$1") (pintype "input"))
    )
    (net (code "53") (name "Net-(TP213-TP)") (class "Default")
      (node (ref "J207") (pin "1") (pinfunction "1_1") (pintype "passive"))
      (node (ref "TP213") (pin "P$1") (pinfunction "TP_P$1") (pintype "input"))
    )
    (net (code "54") (name "Net-(TP214-TP)") (class "Default")
      (node (ref "J207") (pin "2") (pinfunction "2_2") (pintype "passive"))
      (node (ref "TP214") (pin "P$1") (pinfunction "TP_P$1") (pintype "input"))
    )
    (net (code "55") (name "Net-(TP215-TP)") (class "Default")
      (node (ref "J208") (pin "1") (pinfunction "1_1") (pintype "passive"))
      (node (ref "TP215") (pin "P$1") (pinfunction "TP_P$1") (pintype "input"))
    )
    (net (code "56") (name "Net-(TP216-TP)") (class "Default")
      (node (ref "J208") (pin "2") (pinfunction "2_2") (pintype "passive"))
      (node (ref "TP216") (pin "P$1") (pinfunction "TP_P$1") (pintype "input"))
    )
    (net (code "57") (name "Net-(TP217-TP)") (class "Default")
      (node (ref "J209") (pin "1") (pinfunction "1_1") (pintype "passive"))
      (node (ref "TP217") (pin "P$1") (pinfunction "TP_P$1") (pintype "input"))
    )
    (net (code "58") (name "Net-(TP218-TP)") (class "Default")
      (node (ref "J209") (pin "2") (pinfunction "2_2") (pintype "passive"))
      (node (ref "TP218") (pin "P$1") (pinfunction "TP_P$1") (pintype "input"))
    )
    (net (code "59") (name "Net-(TP219-TP)") (class "Default")
      (node (ref "J210") (pin "1") (pinfunction "1_1") (pintype "passive"))
      (node (ref "TP219") (pin "P$1") (pinfunction "TP_P$1") (pintype "input"))
    )
    (net (code "60") (name "Net-(TP220-TP)") (class "Default")
      (node (ref "J210") (pin "2") (pinfunction "2_2") (pintype "passive"))
      (node (ref "TP220") (pin "P$1") (pinfunction "TP_P$1") (pintype "input"))
    )
    (net (code "61") (name "Net-(TP221-TP)") (class "Default")
      (node (ref "J211") (pin "1") (pinfunction "1_1") (pintype "passive"))
      (node (ref "TP221") (pin "P$1") (pinfunction "TP_P$1") (pintype "input"))
    )
    (net (code "62") (name "Net-(TP222-TP)") (class "Default")
      (node (ref "J211") (pin "2") (pinfunction "2_2") (pintype "passive"))
      (node (ref "TP222") (pin "P$1") (pinfunction "TP_P$1") (pintype "input"))
    )
    (net (code "63") (name "Net-(TP223-TP)") (class "Default")
      (node (ref "J212") (pin "1") (pinfunction "1_1") (pintype "passive"))
      (node (ref "TP223") (pin "P$1") (pinfunction "TP_P$1") (pintype "input"))
    )
    (net (code "64") (name "Net-(TP224-TP)") (class "Default")
      (node (ref "J212") (pin "2") (pinfunction "2_2") (pintype "passive"))
      (node (ref "TP224") (pin "P$1") (pinfunction "TP_P$1") (pintype "input"))
    )
    (net (code "65") (name "Net-(TP225-TP)") (class "Default")
      (node (ref "J213") (pin "1") (pinfunction "1_1") (pintype "passive"))
      (node (ref "TP225") (pin "P$1") (pinfunction "TP_P$1") (pintype "input"))
    )
    (net (code "66") (name "Net-(TP226-TP)") (class "Default")
      (node (ref "J213") (pin "2") (pinfunction "2_2") (pintype "passive"))
      (node (ref "TP226") (pin "P$1") (pinfunction "TP_P$1") (pintype "input"))
    )
    (net (code "67") (name "Net-(TP227-TP)") (class "Default")
      (node (ref "J214") (pin "1") (pinfunction "1_1") (pintype "passive"))
      (node (ref "TP227") (pin "P$1") (pinfunction "TP_P$1") (pintype "input"))
    )
    (net (code "68") (name "Net-(TP228-TP)") (class "Default")
      (node (ref "J214") (pin "2") (pinfunction "2_2") (pintype "passive"))
      (node (ref "TP228") (pin "P$1") (pinfunction "TP_P$1") (pintype "input"))
    )
    (net (code "69") (name "SCK") (class "Default")
      (node (ref "J101") (pin "11") (pinfunction "11_11") (pintype "passive"))
      (node (ref "J102") (pin "11") (pinfunction "11_11") (pintype "passive"))
      (node (ref "J103") (pin "11") (pinfunction "11_11") (pintype "passive"))
      (node (ref "J104") (pin "11") (pinfunction "11_11") (pintype "passive"))
      (node (ref "J105") (pin "11") (pinfunction "11_11") (pintype "passive"))
      (node (ref "J106") (pin "11") (pinfunction "11_11") (pintype "passive"))
      (node (ref "J107") (pin "11") (pinfunction "11_11") (pintype "passive"))
      (node (ref "J111") (pin "4") (pinfunction "4_4") (pintype "passive"))
    )
    (net (code "70") (name "THYONE_B1") (class "Default")
      (node (ref "J109") (pin "5") (pinfunction "3_5") (pintype "passive"))
    )
    (net (code "71") (name "THYONE_B2") (class "Default")
      (node (ref "J109") (pin "6") (pinfunction "14_6") (pintype "passive"))
    )
    (net (code "72") (name "THYONE_B3") (class "Default")
      (node (ref "J109") (pin "8") (pinfunction "13_8") (pintype "passive"))
    )
    (net (code "73") (name "THYONE_B4") (class "Default")
      (node (ref "J109") (pin "7") (pinfunction "4_7") (pintype "passive"))
    )
    (net (code "74") (name "THYONE_B5") (class "Default")
      (node (ref "J109") (pin "9") (pinfunction "5_9") (pintype "passive"))
    )
    (net (code "75") (name "THYONE_B6") (class "Default")
      (node (ref "J109") (pin "10") (pinfunction "12_10") (pintype "passive"))
    )
    (net (code "76") (name "THYONE_BUSY") (class "Default")
      (node (ref "J109") (pin "12") (pinfunction "11_12") (pintype "passive"))
    )
    (net (code "77") (name "THYONE_CTS") (class "Default")
      (node (ref "J109") (pin "15") (pinfunction "8_15") (pintype "passive"))
      (node (ref "J110") (pin "7") (pinfunction "7_7") (pintype "passive"))
    )
    (net (code "78") (name "THYONE_MAIN2THYONE") (class "Default")
      (node (ref "J109") (pin "14") (pinfunction "10_14") (pintype "passive"))
      (node (ref "J110") (pin "9") (pinfunction "9_9") (pintype "passive"))
    )
    (net (code "79") (name "THYONE_MODE1") (class "Default")
      (node (ref "J109") (pin "11") (pinfunction "6_11") (pintype "passive"))
    )
    (net (code "80") (name "THYONE_NRST") (class "Default")
      (node (ref "J109") (pin "4") (pinfunction "15_4") (pintype "passive"))
    )
    (net (code "81") (name "THYONE_RTS") (class "Default")
      (node (ref "J109") (pin "16") (pinfunction "9_16") (pintype "passive"))
      (node (ref "J110") (pin "16") (pinfunction "16_16") (pintype "passive"))
    )
    (net (code "82") (name "THYONE_THYONE2MAIN") (class "Default")
      (node (ref "J109") (pin "13") (pinfunction "7_13") (pintype "passive"))
      (node (ref "J110") (pin "8") (pinfunction "8_8") (pintype "passive"))
    )
    (net (code "83") (name "THYONE_WAKEUP") (class "Default")
      (node (ref "J109") (pin "3") (pinfunction "2_3") (pintype "passive"))
    )
    (net (code "84") (name "UNUSED_EXTI_GPIO") (class "Default")
      (node (ref "J111") (pin "10") (pinfunction "10_10") (pintype "passive"))
    )
    (net (code "85") (name "VCC") (class "Default")
      (node (ref "J101") (pin "1") (pinfunction "1_1") (pintype "passive"))
      (node (ref "J102") (pin "1") (pinfunction "1_1") (pintype "passive"))
      (node (ref "J103") (pin "1") (pinfunction "1_1") (pintype "passive"))
      (node (ref "J104") (pin "1") (pinfunction "1_1") (pintype "passive"))
      (node (ref "J105") (pin "1") (pinfunction "1_1") (pintype "passive"))
      (node (ref "J106") (pin "1") (pinfunction "1_1") (pintype "passive"))
      (node (ref "J107") (pin "1") (pinfunction "1_1") (pintype "passive"))
      (node (ref "J110") (pin "3") (pinfunction "3_3") (pintype "passive"))
      (node (ref "J111") (pin "16") (pinfunction "16_16") (pintype "passive"))
    )
    (net (code "86") (name "unconnected-(J201-Pad3)") (class "Default")
      (node (ref "J201") (pin "3") (pinfunction "3_3") (pintype "passive"))
    )
    (net (code "87") (name "unconnected-(J201-Pad4)") (class "Default")
      (node (ref "J201") (pin "4") (pinfunction "4_4") (pintype "passive"))
    )
    (net (code "88") (name "unconnected-(J202-Pad3)") (class "Default")
      (node (ref "J202") (pin "3") (pinfunction "3_3") (pintype "passive"))
    )
    (net (code "89") (name "unconnected-(J202-Pad4)") (class "Default")
      (node (ref "J202") (pin "4") (pinfunction "4_4") (pintype "passive"))
    )
    (net (code "90") (name "unconnected-(J203-Pad3)") (class "Default")
      (node (ref "J203") (pin "3") (pinfunction "3_3") (pintype "passive"))
    )
    (net (code "91") (name "unconnected-(J203-Pad4)") (class "Default")
      (node (ref "J203") (pin "4") (pinfunction "4_4") (pintype "passive"))
    )
    (net (code "92") (name "unconnected-(J204-Pad3)") (class "Default")
      (node (ref "J204") (pin "3") (pinfunction "3_3") (pintype "passive"))
    )
    (net (code "93") (name "unconnected-(J204-Pad4)") (class "Default")
      (node (ref "J204") (pin "4") (pinfunction "4_4") (pintype "passive"))
    )
    (net (code "94") (name "unconnected-(J205-Pad3)") (class "Default")
      (node (ref "J205") (pin "3") (pinfunction "3_3") (pintype "passive"))
    )
    (net (code "95") (name "unconnected-(J205-Pad4)") (class "Default")
      (node (ref "J205") (pin "4") (pinfunction "4_4") (pintype "passive"))
    )
    (net (code "96") (name "unconnected-(J206-Pad3)") (class "Default")
      (node (ref "J206") (pin "3") (pinfunction "3_3") (pintype "passive"))
    )
    (net (code "97") (name "unconnected-(J206-Pad4)") (class "Default")
      (node (ref "J206") (pin "4") (pinfunction "4_4") (pintype "passive"))
    )
    (net (code "98") (name "unconnected-(J207-Pad3)") (class "Default")
      (node (ref "J207") (pin "3") (pinfunction "3_3") (pintype "passive"))
    )
    (net (code "99") (name "unconnected-(J207-Pad4)") (class "Default")
      (node (ref "J207") (pin "4") (pinfunction "4_4") (pintype "passive"))
    )
    (net (code "100") (name "unconnected-(J208-Pad3)") (class "Default")
      (node (ref "J208") (pin "3") (pinfunction "3_3") (pintype "passive"))
    )
    (net (code "101") (name "unconnected-(J208-Pad4)") (class "Default")
      (node (ref "J208") (pin "4") (pinfunction "4_4") (pintype "passive"))
    )
    (net (code "102") (name "unconnected-(J209-Pad3)") (class "Default")
      (node (ref "J209") (pin "3") (pinfunction "3_3") (pintype "passive"))
    )
    (net (code "103") (name "unconnected-(J209-Pad4)") (class "Default")
      (node (ref "J209") (pin "4") (pinfunction "4_4") (pintype "passive"))
    )
    (net (code "104") (name "unconnected-(J210-Pad3)") (class "Default")
      (node (ref "J210") (pin "3") (pinfunction "3_3") (pintype "passive"))
    )
    (net (code "105") (name "unconnected-(J210-Pad4)") (class "Default")
      (node (ref "J210") (pin "4") (pinfunction "4_4") (pintype "passive"))
    )
    (net (code "106") (name "unconnected-(J211-Pad3)") (class "Default")
      (node (ref "J211") (pin "3") (pinfunction "3_3") (pintype "passive"))
    )
    (net (code "107") (name "unconnected-(J211-Pad4)") (class "Default")
      (node (ref "J211") (pin "4") (pinfunction "4_4") (pintype "passive"))
    )
    (net (code "108") (name "unconnected-(J212-Pad3)") (class "Default")
      (node (ref "J212") (pin "3") (pinfunction "3_3") (pintype "passive"))
    )
    (net (code "109") (name "unconnected-(J212-Pad4)") (class "Default")
      (node (ref "J212") (pin "4") (pinfunction "4_4") (pintype "passive"))
    )
    (net (code "110") (name "unconnected-(J213-Pad3)") (class "Default")
      (node (ref "J213") (pin "3") (pinfunction "3_3") (pintype "passive"))
    )
    (net (code "111") (name "unconnected-(J213-Pad4)") (class "Default")
      (node (ref "J213") (pin "4") (pinfunction "4_4") (pintype "passive"))
    )
    (net (code "112") (name "unconnected-(J214-Pad3)") (class "Default")
      (node (ref "J214") (pin "3") (pinfunction "3_3") (pintype "passive"))
    )
    (net (code "113") (name "unconnected-(J214-Pad4)") (class "Default")
      (node (ref "J214") (pin "4") (pinfunction "4_4") (pintype "passive"))
    )
  )
)
